# RTC_SCH.net
KiCad netlist of a schematic drawn in Altium Designer
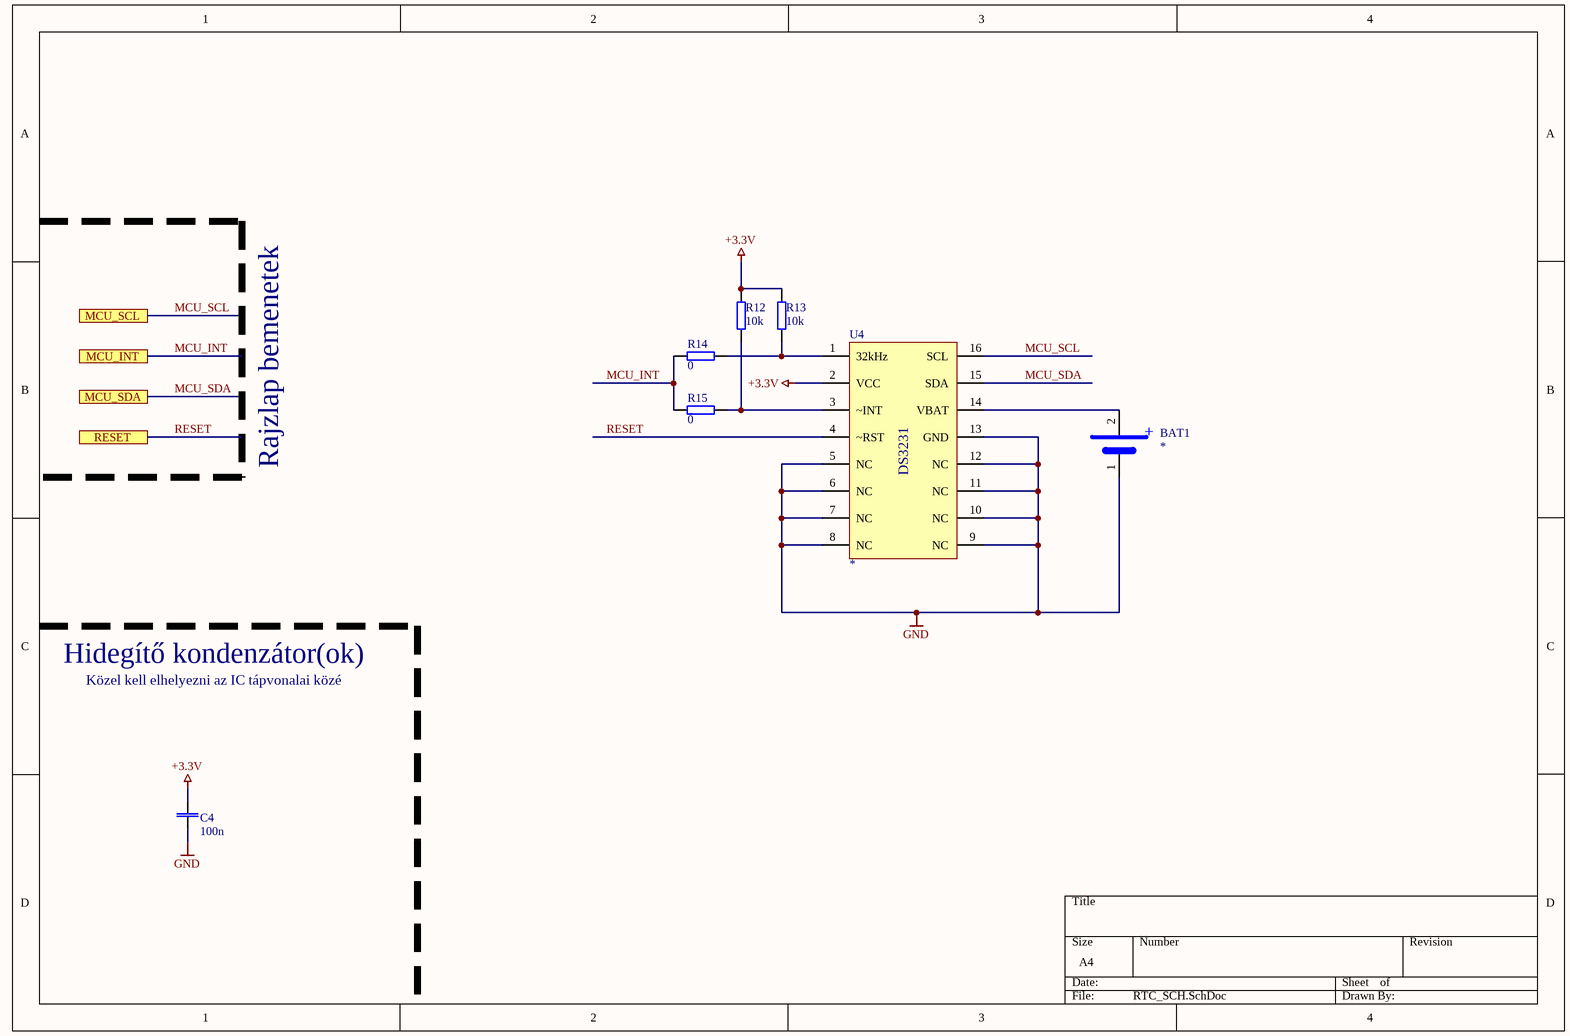
[diagram p0: RTC_SCH.SchDoc]

(export (version "E")
  (design (tool "Eeschema 10.0.6"))
  (components
    (comp (ref "BAT1")
      (value "*")
      (footprint "CR2032")
      (description "battery")
      (libsource (lib "SCH_LIB") (part "Battery"))
    )
    (comp (ref "C4")
      (value "100n")
      (footprint "CAP 0805")
      (description "NON POLARIZED CAPACITOR")
      (libsource (lib "SCH_LIB") (part "CAP"))
    )
    (comp (ref "R12")
      (value "10k")
      (footprint "RES 0805")
      (description "RESISTOR")
      (libsource (lib "") (part "RES_1"))
    )
    (comp (ref "R13")
      (value "10k")
      (footprint "RES 0805")
      (description "RESISTOR")
      (libsource (lib "") (part "RES_1"))
    )
    (comp (ref "R14")
      (value "0")
      (footprint "RES 0805")
      (description "RESISTOR")
      (libsource (lib "SCH_LIB") (part "RES"))
    )
    (comp (ref "R15")
      (value "0")
      (footprint "RES 0805")
      (description "RESISTOR")
      (libsource (lib "SCH_LIB") (part "RES"))
    )
    (comp (ref "U4")
      (value "*")
      (footprint "SO16W")
      (description "3.3V Real Time Clock IC")
      (libsource (lib "SCH_LIB") (part "DS3231"))
    )
  )
  (nets
    (net (code "1") (name "+3.3V") (class "Default")
      (node (ref "C4") (pin "2") (pinfunction "2_2") (pintype "passive"))
      (node (ref "R12") (pin "2") (pinfunction "2_2") (pintype "passive"))
      (node (ref "R13") (pin "2") (pinfunction "2_2") (pintype "passive"))
      (node (ref "U4") (pin "2") (pinfunction "VCC_2") (pintype "passive"))
    )
    (net (code "2") (name "/MCU_INT") (class "Default")
      (node (ref "R14") (pin "2") (pinfunction "2_2") (pintype "passive"))
      (node (ref "R15") (pin "2") (pinfunction "2_2") (pintype "passive"))
    )
    (net (code "3") (name "/MCU_SCL") (class "Default")
      (node (ref "U4") (pin "16") (pinfunction "SCL_16") (pintype "passive"))
    )
    (net (code "4") (name "/MCU_SDA") (class "Default")
      (node (ref "U4") (pin "15") (pinfunction "SDA_15") (pintype "passive"))
    )
    (net (code "5") (name "/RESET") (class "Default")
      (node (ref "U4") (pin "4") (pinfunction "~RST_4") (pintype "passive"))
    )
    (net (code "6") (name "GND") (class "Default")
      (node (ref "BAT1") (pin "1") (pintype "passive"))
      (node (ref "C4") (pin "1") (pinfunction "1_1") (pintype "passive"))
      (node (ref "U4") (pin "10") (pinfunction "NC_10") (pintype "passive"))
      (node (ref "U4") (pin "11") (pinfunction "NC_11") (pintype "passive"))
      (node (ref "U4") (pin "12") (pinfunction "NC_12") (pintype "passive"))
      (node (ref "U4") (pin "13") (pinfunction "GND_13") (pintype "passive"))
      (node (ref "U4") (pin "5") (pinfunction "NC_5") (pintype "passive"))
      (node (ref "U4") (pin "6") (pinfunction "NC_6") (pintype "passive"))
      (node (ref "U4") (pin "7") (pinfunction "NC_7") (pintype "passive"))
      (node (ref "U4") (pin "8") (pinfunction "NC_8") (pintype "passive"))
      (node (ref "U4") (pin "9") (pinfunction "NC_9") (pintype "passive"))
    )
    (net (code "7") (name "Net-(U4-32kHz)") (class "Default")
      (node (ref "R13") (pin "1") (pinfunction "1_1") (pintype "passive"))
      (node (ref "R14") (pin "1") (pinfunction "1_1") (pintype "passive"))
      (node (ref "U4") (pin "1") (pinfunction "32kHz_1") (pintype "passive"))
    )
    (net (code "8") (name "Net-(U4-VBAT)") (class "Default")
      (node (ref "BAT1") (pin "2") (pintype "passive"))
      (node (ref "U4") (pin "14") (pinfunction "VBAT_14") (pintype "passive"))
    )
    (net (code "9") (name "Net-(U4-~INT)") (class "Default")
      (node (ref "R12") (pin "1") (pinfunction "1_1") (pintype "passive"))
      (node (ref "R15") (pin "1") (pinfunction "1_1") (pintype "passive"))
      (node (ref "U4") (pin "3") (pinfunction "~INT_3") (pintype "passive"))
    )
  )
)
